# OpAmpDiffHS.net
KiCad netlist of a schematic drawn in Altium Designer
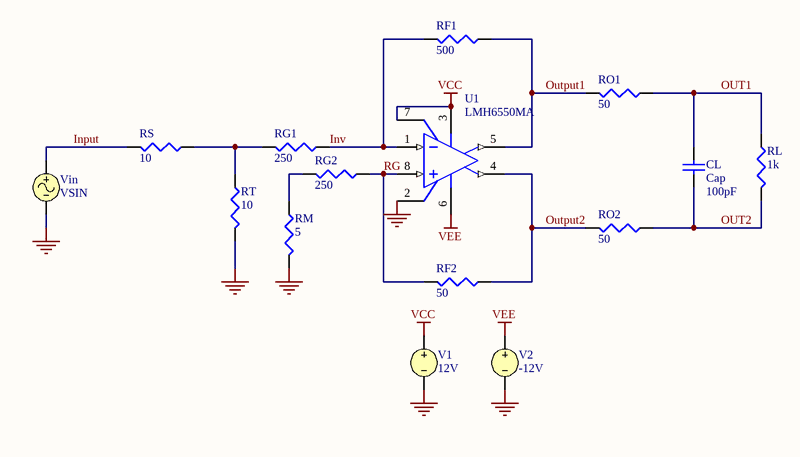
[diagram p0: OpAmpDiffHS.schdoc]

(export (version "E")
  (design (tool "Eeschema 10.0.6"))
  (components
    (comp (ref "CL")
      (value "Cap")
      (footprint "RAD-0.3")
      (description "Capacitor")
      (fields (field (name "ALTIUM_VALUE") "100pF") (field (name "PUBLISHER") "Altium Limited"))
      (libsource (lib "Miscellaneous Devices") (part "Cap"))
    )
    (comp (ref "RF1")
      (value "500")
      (description "Resistor")
      (fields (field (name "Comment") "100k"))
      (libsource (lib "*") (part "RES"))
    )
    (comp (ref "RF2")
      (value "50")
      (description "Resistor")
      (fields (field (name "Comment") "100k"))
      (libsource (lib "*") (part "RES"))
    )
    (comp (ref "RG1")
      (value "250")
      (description "Resistor")
      (fields (field (name "Comment") "10k"))
      (libsource (lib "*") (part "RES"))
    )
    (comp (ref "RG2")
      (value "250")
      (description "Resistor")
      (fields (field (name "Comment") "10k"))
      (libsource (lib "*") (part "RES"))
    )
    (comp (ref "RL")
      (value "1k")
      (description "Resistor")
      (fields (field (name "Comment") "25k"))
      (libsource (lib "") (part "RES_1"))
    )
    (comp (ref "RM")
      (value "5")
      (description "Resistor")
      (fields (field (name "Comment") "10k"))
      (libsource (lib "") (part "RES_1"))
    )
    (comp (ref "RO1")
      (value "50")
      (description "Resistor")
      (fields (field (name "Comment") "25k"))
      (libsource (lib "*") (part "RES"))
    )
    (comp (ref "RO2")
      (value "50")
      (description "Resistor")
      (fields (field (name "Comment") "25k"))
      (libsource (lib "*") (part "RES"))
    )
    (comp (ref "RS")
      (value "10")
      (description "Resistor")
      (fields (field (name "Comment") "10k"))
      (libsource (lib "*") (part "RES"))
    )
    (comp (ref "RT")
      (value "10")
      (description "Resistor")
      (fields (field (name "Comment") "10k"))
      (libsource (lib "") (part "RES_1"))
    )
    (comp (ref "U1")
      (value "LMH6550MA")
      (footprint "M08A_N")
      (description "Differential, High Speed Op Amp")
      (fields
        (field (name "MANUFACTURER") "National Semiconductor")
        (field (name "DIGIKEYPARTNUMBER") "LMH6550MA-ND")
        (field (name "PUBLISHER") "Altium Limited")
      )
      (libsource (lib "NSC Amplifier with SIM models") (part "LMH6550MA"))
    )
    (comp (ref "V1") (value "12V") (description "Voltage Source") (libsource (lib "*") (part "VSRC")))
    (comp (ref "V2") (value "-12V") (description "Voltage Source") (libsource (lib "*") (part "VSRC")))
    (comp (ref "Vin")
      (value "VSIN")
      (description "Sinusoidal Voltage Source")
      (libsource (lib "*") (part "VSIN"))
    )
  )
  (nets
    (net (code "1") (name "/Input") (class "Default")
      (node (ref "RS") (pin "1") (pinfunction "TOP_1") (pintype "passive"))
      (node (ref "Vin") (pin "1") (pinfunction "1_1") (pintype "passive"))
    )
    (net (code "2") (name "/Inv") (class "Default")
      (node (ref "RF1") (pin "1") (pinfunction "TOP_1") (pintype "passive"))
      (node (ref "RG1") (pin "2") (pinfunction "BOT_2") (pintype "passive"))
      (node (ref "U1") (pin "1") (pinfunction "IN-_1") (pintype "input"))
    )
    (net (code "3") (name "/OUT1") (class "Default")
      (node (ref "CL") (pin "2") (pinfunction "2_2") (pintype "passive"))
      (node (ref "RL") (pin "2") (pinfunction "BOT_2") (pintype "passive"))
      (node (ref "RO1") (pin "2") (pinfunction "BOT_2") (pintype "passive"))
    )
    (net (code "4") (name "/OUT2") (class "Default")
      (node (ref "CL") (pin "1") (pinfunction "1_1") (pintype "passive"))
      (node (ref "RL") (pin "1") (pinfunction "TOP_1") (pintype "passive"))
      (node (ref "RO2") (pin "2") (pinfunction "BOT_2") (pintype "passive"))
    )
    (net (code "5") (name "/Output1") (class "Default")
      (node (ref "RF1") (pin "2") (pinfunction "BOT_2") (pintype "passive"))
      (node (ref "RO1") (pin "1") (pinfunction "TOP_1") (pintype "passive"))
      (node (ref "U1") (pin "5") (pinfunction "OUT-_5") (pintype "output"))
    )
    (net (code "6") (name "/Output2") (class "Default")
      (node (ref "RF2") (pin "2") (pinfunction "BOT_2") (pintype "passive"))
      (node (ref "RO2") (pin "1") (pinfunction "TOP_1") (pintype "passive"))
      (node (ref "U1") (pin "4") (pinfunction "OUT+_4") (pintype "output"))
    )
    (net (code "7") (name "/RG") (class "Default")
      (node (ref "RF2") (pin "1") (pinfunction "TOP_1") (pintype "passive"))
      (node (ref "RG2") (pin "2") (pinfunction "BOT_2") (pintype "passive"))
      (node (ref "U1") (pin "8") (pinfunction "IN+_8") (pintype "input"))
    )
    (net (code "8") (name "GND") (class "Default")
      (node (ref "RM") (pin "1") (pinfunction "TOP_1") (pintype "passive"))
      (node (ref "RT") (pin "1") (pinfunction "TOP_1") (pintype "passive"))
      (node (ref "U1") (pin "2") (pinfunction "VCM_2") (pintype "passive"))
      (node (ref "V1") (pin "2") (pinfunction "2_2") (pintype "passive"))
      (node (ref "V2") (pin "2") (pinfunction "2_2") (pintype "passive"))
      (node (ref "Vin") (pin "2") (pinfunction "2_2") (pintype "passive"))
    )
    (net (code "9") (name "Net-(RG1-TOP)") (class "Default")
      (node (ref "RG1") (pin "1") (pinfunction "TOP_1") (pintype "passive"))
      (node (ref "RS") (pin "2") (pinfunction "BOT_2") (pintype "passive"))
      (node (ref "RT") (pin "2") (pinfunction "BOT_2") (pintype "passive"))
    )
    (net (code "10") (name "Net-(RG2-TOP)") (class "Default")
      (node (ref "RG2") (pin "1") (pinfunction "TOP_1") (pintype "passive"))
      (node (ref "RM") (pin "2") (pinfunction "BOT_2") (pintype "passive"))
    )
    (net (code "11") (name "VCC") (class "Default")
      (node (ref "U1") (pin "3") (pinfunction "V+_3") (pintype "power_in"))
      (node (ref "U1") (pin "7") (pinfunction "EN_7") (pintype "passive"))
      (node (ref "V1") (pin "1") (pinfunction "1_1") (pintype "passive"))
    )
    (net (code "12") (name "VEE") (class "Default")
      (node (ref "U1") (pin "6") (pinfunction "V-_6") (pintype "power_in"))
      (node (ref "V2") (pin "1") (pinfunction "1_1") (pintype "passive"))
    )
  )
)
